# MEGA_shield_PORTS.net
KiCad netlist of a schematic drawn in EAGLE
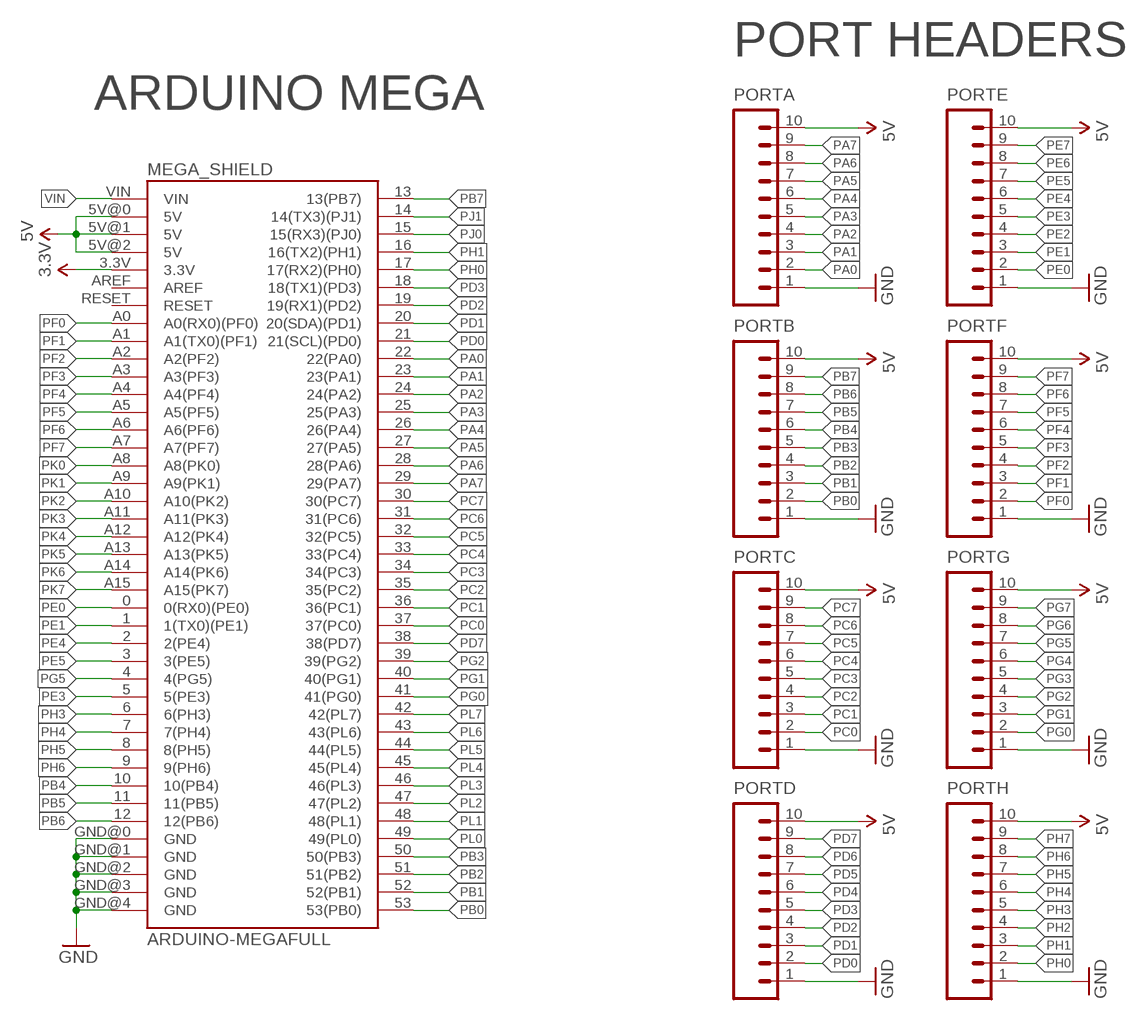
[diagram p0: schematic, sheet 1]

(export (version "E")
  (design (tool "Eeschema 10.0.6"))
  (components
    (comp (ref "MEGA_SHIELD")
      (value "ARDUINO-MEGAFULL")
      (footprint "eagle-import:ARDUINO_MEGA")
      (libsource (lib "eagle-import") (part "ARDUINO-MEGAFULL"))
    )
    (comp (ref "PORTA")
      (value "M10NO_SILK_PTH_FEMALE")
      (footprint "eagle-import:1X10_NO_SILK")
      (libsource (lib "eagle-import") (part "M10NO_SILK_PTH_FEMALE"))
    )
    (comp (ref "PORTB")
      (value "M10NO_SILK_PTH_FEMALE")
      (footprint "eagle-import:1X10_NO_SILK")
      (libsource (lib "eagle-import") (part "M10NO_SILK_PTH_FEMALE"))
    )
    (comp (ref "PORTC")
      (value "M10NO_SILK_PTH_FEMALE")
      (footprint "eagle-import:1X10_NO_SILK")
      (libsource (lib "eagle-import") (part "M10NO_SILK_PTH_FEMALE"))
    )
    (comp (ref "PORTD")
      (value "M10NO_SILK_PTH_FEMALE")
      (footprint "eagle-import:1X10_NO_SILK")
      (libsource (lib "eagle-import") (part "M10NO_SILK_PTH_FEMALE"))
    )
    (comp (ref "PORTE")
      (value "M10NO_SILK_PTH_FEMALE")
      (footprint "eagle-import:1X10_NO_SILK")
      (libsource (lib "eagle-import") (part "M10NO_SILK_PTH_FEMALE"))
    )
    (comp (ref "PORTF")
      (value "M10NO_SILK_PTH_FEMALE")
      (footprint "eagle-import:1X10_NO_SILK")
      (libsource (lib "eagle-import") (part "M10NO_SILK_PTH_FEMALE"))
    )
    (comp (ref "PORTG")
      (value "M10NO_SILK_PTH_FEMALE")
      (footprint "eagle-import:1X10_NO_SILK")
      (libsource (lib "eagle-import") (part "M10NO_SILK_PTH_FEMALE"))
    )
    (comp (ref "PORTH")
      (value "M10NO_SILK_PTH_FEMALE")
      (footprint "eagle-import:1X10_NO_SILK")
      (libsource (lib "eagle-import") (part "M10NO_SILK_PTH_FEMALE"))
    )
  )
  (nets
    (net (code "1") (name "3.3V") (class "Default")
      (node (ref "MEGA_SHIELD") (pin "3.3V") (pinfunction "3.3V_3.3V") (pintype "bidirectional"))
    )
    (net (code "2") (name "5V") (class "Default")
      (node (ref "MEGA_SHIELD") (pin "5V@0") (pinfunction "5V_5V@0") (pintype "bidirectional"))
      (node (ref "MEGA_SHIELD") (pin "5V@1") (pinfunction "5V_5V@1") (pintype "bidirectional"))
      (node (ref "MEGA_SHIELD") (pin "5V@2") (pinfunction "5V_5V@2") (pintype "bidirectional"))
      (node (ref "PORTA") (pin "10") (pinfunction "10_10") (pintype "passive"))
      (node (ref "PORTB") (pin "10") (pinfunction "10_10") (pintype "passive"))
      (node (ref "PORTC") (pin "10") (pinfunction "10_10") (pintype "passive"))
      (node (ref "PORTD") (pin "10") (pinfunction "10_10") (pintype "passive"))
      (node (ref "PORTE") (pin "10") (pinfunction "10_10") (pintype "passive"))
      (node (ref "PORTF") (pin "10") (pinfunction "10_10") (pintype "passive"))
      (node (ref "PORTG") (pin "10") (pinfunction "10_10") (pintype "passive"))
      (node (ref "PORTH") (pin "10") (pinfunction "10_10") (pintype "passive"))
    )
    (net (code "3") (name "GND") (class "Default")
      (node (ref "MEGA_SHIELD") (pin "GND@0") (pinfunction "GND_GND@0") (pintype "bidirectional"))
      (node (ref "MEGA_SHIELD") (pin "GND@1") (pinfunction "GND_GND@1") (pintype "bidirectional"))
      (node (ref "MEGA_SHIELD") (pin "GND@2") (pinfunction "GND_GND@2") (pintype "bidirectional"))
      (node (ref "MEGA_SHIELD") (pin "GND@3") (pinfunction "GND_GND@3") (pintype "bidirectional"))
      (node (ref "MEGA_SHIELD") (pin "GND@4") (pinfunction "GND_GND@4") (pintype "bidirectional"))
      (node (ref "PORTA") (pin "1") (pinfunction "1_1") (pintype "passive"))
      (node (ref "PORTB") (pin "1") (pinfunction "1_1") (pintype "passive"))
      (node (ref "PORTC") (pin "1") (pinfunction "1_1") (pintype "passive"))
      (node (ref "PORTD") (pin "1") (pinfunction "1_1") (pintype "passive"))
      (node (ref "PORTE") (pin "1") (pinfunction "1_1") (pintype "passive"))
      (node (ref "PORTF") (pin "1") (pinfunction "1_1") (pintype "passive"))
      (node (ref "PORTG") (pin "1") (pinfunction "1_1") (pintype "passive"))
      (node (ref "PORTH") (pin "1") (pinfunction "1_1") (pintype "passive"))
    )
    (net (code "4") (name "PA0") (class "Default")
      (node (ref "MEGA_SHIELD") (pin "22") (pinfunction "22(PA0)_22") (pintype "bidirectional"))
      (node (ref "PORTA") (pin "2") (pinfunction "2_2") (pintype "passive"))
    )
    (net (code "5") (name "PA1") (class "Default")
      (node (ref "MEGA_SHIELD") (pin "23") (pinfunction "23(PA1)_23") (pintype "bidirectional"))
      (node (ref "PORTA") (pin "3") (pinfunction "3_3") (pintype "passive"))
    )
    (net (code "6") (name "PA2") (class "Default")
      (node (ref "MEGA_SHIELD") (pin "24") (pinfunction "24(PA2)_24") (pintype "bidirectional"))
      (node (ref "PORTA") (pin "4") (pinfunction "4_4") (pintype "passive"))
    )
    (net (code "7") (name "PA3") (class "Default")
      (node (ref "MEGA_SHIELD") (pin "25") (pinfunction "25(PA3)_25") (pintype "bidirectional"))
      (node (ref "PORTA") (pin "5") (pinfunction "5_5") (pintype "passive"))
    )
    (net (code "8") (name "PA4") (class "Default")
      (node (ref "MEGA_SHIELD") (pin "26") (pinfunction "26(PA4)_26") (pintype "bidirectional"))
      (node (ref "PORTA") (pin "6") (pinfunction "6_6") (pintype "passive"))
    )
    (net (code "9") (name "PA5") (class "Default")
      (node (ref "MEGA_SHIELD") (pin "27") (pinfunction "27(PA5)_27") (pintype "bidirectional"))
      (node (ref "PORTA") (pin "7") (pinfunction "7_7") (pintype "passive"))
    )
    (net (code "10") (name "PA6") (class "Default")
      (node (ref "MEGA_SHIELD") (pin "28") (pinfunction "28(PA6)_28") (pintype "bidirectional"))
      (node (ref "PORTA") (pin "8") (pinfunction "8_8") (pintype "passive"))
    )
    (net (code "11") (name "PA7") (class "Default")
      (node (ref "MEGA_SHIELD") (pin "29") (pinfunction "29(PA7)_29") (pintype "bidirectional"))
      (node (ref "PORTA") (pin "9") (pinfunction "9_9") (pintype "passive"))
    )
    (net (code "12") (name "PB0") (class "Default")
      (node (ref "MEGA_SHIELD") (pin "53") (pinfunction "53(PB0)_53") (pintype "bidirectional"))
      (node (ref "PORTB") (pin "2") (pinfunction "2_2") (pintype "passive"))
    )
    (net (code "13") (name "PB1") (class "Default")
      (node (ref "MEGA_SHIELD") (pin "52") (pinfunction "52(PB1)_52") (pintype "bidirectional"))
      (node (ref "PORTB") (pin "3") (pinfunction "3_3") (pintype "passive"))
    )
    (net (code "14") (name "PB2") (class "Default")
      (node (ref "MEGA_SHIELD") (pin "51") (pinfunction "51(PB2)_51") (pintype "bidirectional"))
      (node (ref "PORTB") (pin "4") (pinfunction "4_4") (pintype "passive"))
    )
    (net (code "15") (name "PB3") (class "Default")
      (node (ref "MEGA_SHIELD") (pin "50") (pinfunction "50(PB3)_50") (pintype "bidirectional"))
      (node (ref "PORTB") (pin "5") (pinfunction "5_5") (pintype "passive"))
    )
    (net (code "16") (name "PB4") (class "Default")
      (node (ref "MEGA_SHIELD") (pin "10") (pinfunction "10(PB4)_10") (pintype "bidirectional"))
      (node (ref "PORTB") (pin "6") (pinfunction "6_6") (pintype "passive"))
    )
    (net (code "17") (name "PB5") (class "Default")
      (node (ref "MEGA_SHIELD") (pin "11") (pinfunction "11(PB5)_11") (pintype "bidirectional"))
      (node (ref "PORTB") (pin "7") (pinfunction "7_7") (pintype "passive"))
    )
    (net (code "18") (name "PB6") (class "Default")
      (node (ref "MEGA_SHIELD") (pin "12") (pinfunction "12(PB6)_12") (pintype "bidirectional"))
      (node (ref "PORTB") (pin "8") (pinfunction "8_8") (pintype "passive"))
    )
    (net (code "19") (name "PB7") (class "Default")
      (node (ref "MEGA_SHIELD") (pin "13") (pinfunction "13(PB7)_13") (pintype "bidirectional"))
      (node (ref "PORTB") (pin "9") (pinfunction "9_9") (pintype "passive"))
    )
    (net (code "20") (name "PC0") (class "Default")
      (node (ref "MEGA_SHIELD") (pin "37") (pinfunction "37(PC0)_37") (pintype "bidirectional"))
      (node (ref "PORTC") (pin "2") (pinfunction "2_2") (pintype "passive"))
    )
    (net (code "21") (name "PC1") (class "Default")
      (node (ref "MEGA_SHIELD") (pin "36") (pinfunction "36(PC1)_36") (pintype "bidirectional"))
      (node (ref "PORTC") (pin "3") (pinfunction "3_3") (pintype "passive"))
    )
    (net (code "22") (name "PC2") (class "Default")
      (node (ref "MEGA_SHIELD") (pin "35") (pinfunction "35(PC2)_35") (pintype "bidirectional"))
      (node (ref "PORTC") (pin "4") (pinfunction "4_4") (pintype "passive"))
    )
    (net (code "23") (name "PC3") (class "Default")
      (node (ref "MEGA_SHIELD") (pin "34") (pinfunction "34(PC3)_34") (pintype "bidirectional"))
      (node (ref "PORTC") (pin "5") (pinfunction "5_5") (pintype "passive"))
    )
    (net (code "24") (name "PC4") (class "Default")
      (node (ref "MEGA_SHIELD") (pin "33") (pinfunction "33(PC4)_33") (pintype "bidirectional"))
      (node (ref "PORTC") (pin "6") (pinfunction "6_6") (pintype "passive"))
    )
    (net (code "25") (name "PC5") (class "Default")
      (node (ref "MEGA_SHIELD") (pin "32") (pinfunction "32(PC5)_32") (pintype "bidirectional"))
      (node (ref "PORTC") (pin "7") (pinfunction "7_7") (pintype "passive"))
    )
    (net (code "26") (name "PC6") (class "Default")
      (node (ref "MEGA_SHIELD") (pin "31") (pinfunction "31(PC6)_31") (pintype "bidirectional"))
      (node (ref "PORTC") (pin "8") (pinfunction "8_8") (pintype "passive"))
    )
    (net (code "27") (name "PC7") (class "Default")
      (node (ref "MEGA_SHIELD") (pin "30") (pinfunction "30(PC7)_30") (pintype "bidirectional"))
      (node (ref "PORTC") (pin "9") (pinfunction "9_9") (pintype "passive"))
    )
    (net (code "28") (name "PD0") (class "Default")
      (node (ref "MEGA_SHIELD") (pin "21") (pinfunction "21(SCL)(PD0)_21") (pintype "bidirectional"))
      (node (ref "PORTD") (pin "2") (pinfunction "2_2") (pintype "passive"))
    )
    (net (code "29") (name "PD1") (class "Default")
      (node (ref "MEGA_SHIELD") (pin "20") (pinfunction "20(SDA)(PD1)_20") (pintype "bidirectional"))
      (node (ref "PORTD") (pin "3") (pinfunction "3_3") (pintype "passive"))
    )
    (net (code "30") (name "PD2") (class "Default")
      (node (ref "MEGA_SHIELD") (pin "19") (pinfunction "19(RX1)(PD2)_19") (pintype "bidirectional"))
      (node (ref "PORTD") (pin "4") (pinfunction "4_4") (pintype "passive"))
    )
    (net (code "31") (name "PD3") (class "Default")
      (node (ref "MEGA_SHIELD") (pin "18") (pinfunction "18(TX1)(PD3)_18") (pintype "bidirectional"))
      (node (ref "PORTD") (pin "5") (pinfunction "5_5") (pintype "passive"))
    )
    (net (code "32") (name "PD4") (class "Default")
      (node (ref "PORTD") (pin "6") (pinfunction "6_6") (pintype "passive"))
    )
    (net (code "33") (name "PD5") (class "Default")
      (node (ref "PORTD") (pin "7") (pinfunction "7_7") (pintype "passive"))
    )
    (net (code "34") (name "PD6") (class "Default")
      (node (ref "PORTD") (pin "8") (pinfunction "8_8") (pintype "passive"))
    )
    (net (code "35") (name "PD7") (class "Default")
      (node (ref "MEGA_SHIELD") (pin "38") (pinfunction "38(PD7)_38") (pintype "bidirectional"))
      (node (ref "PORTD") (pin "9") (pinfunction "9_9") (pintype "passive"))
    )
    (net (code "36") (name "PE0") (class "Default")
      (node (ref "MEGA_SHIELD") (pin "0") (pinfunction "0(RX0)(PE0)_0") (pintype "bidirectional"))
      (node (ref "PORTE") (pin "2") (pinfunction "2_2") (pintype "passive"))
    )
    (net (code "37") (name "PE1") (class "Default")
      (node (ref "MEGA_SHIELD") (pin "1") (pinfunction "1(TX0)(PE1)_1") (pintype "bidirectional"))
      (node (ref "PORTE") (pin "3") (pinfunction "3_3") (pintype "passive"))
    )
    (net (code "38") (name "PE2") (class "Default")
      (node (ref "PORTE") (pin "4") (pinfunction "4_4") (pintype "passive"))
    )
    (net (code "39") (name "PE3") (class "Default")
      (node (ref "MEGA_SHIELD") (pin "5") (pinfunction "5(PE3)_5") (pintype "bidirectional"))
      (node (ref "PORTE") (pin "5") (pinfunction "5_5") (pintype "passive"))
    )
    (net (code "40") (name "PE4") (class "Default")
      (node (ref "MEGA_SHIELD") (pin "2") (pinfunction "2(PE4)_2") (pintype "bidirectional"))
      (node (ref "PORTE") (pin "6") (pinfunction "6_6") (pintype "passive"))
    )
    (net (code "41") (name "PE5") (class "Default")
      (node (ref "MEGA_SHIELD") (pin "3") (pinfunction "3(PE5)_3") (pintype "bidirectional"))
      (node (ref "PORTE") (pin "7") (pinfunction "7_7") (pintype "passive"))
    )
    (net (code "42") (name "PE6") (class "Default")
      (node (ref "PORTE") (pin "8") (pinfunction "8_8") (pintype "passive"))
    )
    (net (code "43") (name "PE7") (class "Default")
      (node (ref "PORTE") (pin "9") (pinfunction "9_9") (pintype "passive"))
    )
    (net (code "44") (name "PF0") (class "Default")
      (node (ref "MEGA_SHIELD") (pin "A0") (pinfunction "A0(RX0)(PF0)_A0") (pintype "bidirectional"))
      (node (ref "PORTF") (pin "2") (pinfunction "2_2") (pintype "passive"))
    )
    (net (code "45") (name "PF1") (class "Default")
      (node (ref "MEGA_SHIELD") (pin "A1") (pinfunction "A1(TX0)(PF1)_A1") (pintype "bidirectional"))
      (node (ref "PORTF") (pin "3") (pinfunction "3_3") (pintype "passive"))
    )
    (net (code "46") (name "PF2") (class "Default")
      (node (ref "MEGA_SHIELD") (pin "A2") (pinfunction "A2(PF2)_A2") (pintype "bidirectional"))
      (node (ref "PORTF") (pin "4") (pinfunction "4_4") (pintype "passive"))
    )
    (net (code "47") (name "PF3") (class "Default")
      (node (ref "MEGA_SHIELD") (pin "A3") (pinfunction "A3(PF3)_A3") (pintype "bidirectional"))
      (node (ref "PORTF") (pin "5") (pinfunction "5_5") (pintype "passive"))
    )
    (net (code "48") (name "PF4") (class "Default")
      (node (ref "MEGA_SHIELD") (pin "A4") (pinfunction "A4(PF4)_A4") (pintype "bidirectional"))
      (node (ref "PORTF") (pin "6") (pinfunction "6_6") (pintype "passive"))
    )
    (net (code "49") (name "PF5") (class "Default")
      (node (ref "MEGA_SHIELD") (pin "A5") (pinfunction "A5(PF5)_A5") (pintype "bidirectional"))
      (node (ref "PORTF") (pin "7") (pinfunction "7_7") (pintype "passive"))
    )
    (net (code "50") (name "PF6") (class "Default")
      (node (ref "MEGA_SHIELD") (pin "A6") (pinfunction "A6(PF6)_A6") (pintype "bidirectional"))
      (node (ref "PORTF") (pin "8") (pinfunction "8_8") (pintype "passive"))
    )
    (net (code "51") (name "PF7") (class "Default")
      (node (ref "MEGA_SHIELD") (pin "A7") (pinfunction "A7(PF7)_A7") (pintype "bidirectional"))
      (node (ref "PORTF") (pin "9") (pinfunction "9_9") (pintype "passive"))
    )
    (net (code "52") (name "PG0") (class "Default")
      (node (ref "MEGA_SHIELD") (pin "41") (pinfunction "41(PG0)_41") (pintype "bidirectional"))
      (node (ref "PORTG") (pin "2") (pinfunction "2_2") (pintype "passive"))
    )
    (net (code "53") (name "PG1") (class "Default")
      (node (ref "MEGA_SHIELD") (pin "40") (pinfunction "40(PG1)_40") (pintype "bidirectional"))
      (node (ref "PORTG") (pin "3") (pinfunction "3_3") (pintype "passive"))
    )
    (net (code "54") (name "PG2") (class "Default")
      (node (ref "MEGA_SHIELD") (pin "39") (pinfunction "39(PG2)_39") (pintype "bidirectional"))
      (node (ref "PORTG") (pin "4") (pinfunction "4_4") (pintype "passive"))
    )
    (net (code "55") (name "PG3") (class "Default")
      (node (ref "PORTG") (pin "5") (pinfunction "5_5") (pintype "passive"))
    )
    (net (code "56") (name "PG4") (class "Default")
      (node (ref "PORTG") (pin "6") (pinfunction "6_6") (pintype "passive"))
    )
    (net (code "57") (name "PG5") (class "Default")
      (node (ref "MEGA_SHIELD") (pin "4") (pinfunction "4(PG5)_4") (pintype "bidirectional"))
      (node (ref "PORTG") (pin "7") (pinfunction "7_7") (pintype "passive"))
    )
    (net (code "58") (name "PG6") (class "Default")
      (node (ref "PORTG") (pin "8") (pinfunction "8_8") (pintype "passive"))
    )
    (net (code "59") (name "PG7") (class "Default")
      (node (ref "PORTG") (pin "9") (pinfunction "9_9") (pintype "passive"))
    )
    (net (code "60") (name "PH0") (class "Default")
      (node (ref "MEGA_SHIELD") (pin "17") (pinfunction "17(RX2)(PH0)_17") (pintype "bidirectional"))
      (node (ref "PORTH") (pin "2") (pinfunction "2_2") (pintype "passive"))
    )
    (net (code "61") (name "PH1") (class "Default")
      (node (ref "MEGA_SHIELD") (pin "16") (pinfunction "16(TX2)(PH1)_16") (pintype "bidirectional"))
      (node (ref "PORTH") (pin "3") (pinfunction "3_3") (pintype "passive"))
    )
    (net (code "62") (name "PH2") (class "Default")
      (node (ref "PORTH") (pin "4") (pinfunction "4_4") (pintype "passive"))
    )
    (net (code "63") (name "PH3") (class "Default")
      (node (ref "MEGA_SHIELD") (pin "6") (pinfunction "6(PH3)_6") (pintype "bidirectional"))
      (node (ref "PORTH") (pin "5") (pinfunction "5_5") (pintype "passive"))
    )
    (net (code "64") (name "PH4") (class "Default")
      (node (ref "MEGA_SHIELD") (pin "7") (pinfunction "7(PH4)_7") (pintype "bidirectional"))
      (node (ref "PORTH") (pin "6") (pinfunction "6_6") (pintype "passive"))
    )
    (net (code "65") (name "PH5") (class "Default")
      (node (ref "MEGA_SHIELD") (pin "8") (pinfunction "8(PH5)_8") (pintype "bidirectional"))
      (node (ref "PORTH") (pin "7") (pinfunction "7_7") (pintype "passive"))
    )
    (net (code "66") (name "PH6") (class "Default")
      (node (ref "MEGA_SHIELD") (pin "9") (pinfunction "9(PH6)_9") (pintype "bidirectional"))
      (node (ref "PORTH") (pin "8") (pinfunction "8_8") (pintype "passive"))
    )
    (net (code "67") (name "PH7") (class "Default")
      (node (ref "PORTH") (pin "9") (pinfunction "9_9") (pintype "passive"))
    )
    (net (code "68") (name "PJ0") (class "Default")
      (node (ref "MEGA_SHIELD") (pin "15") (pinfunction "15(RX3)(PJ0)_15") (pintype "bidirectional"))
    )
    (net (code "69") (name "PJ1") (class "Default")
      (node (ref "MEGA_SHIELD") (pin "14") (pinfunction "14(TX3)(PJ1)_14") (pintype "bidirectional"))
    )
    (net (code "70") (name "PK0") (class "Default")
      (node (ref "MEGA_SHIELD") (pin "A8") (pinfunction "A8(PK0)_A8") (pintype "bidirectional"))
    )
    (net (code "71") (name "PK1") (class "Default")
      (node (ref "MEGA_SHIELD") (pin "A9") (pinfunction "A9(PK1)_A9") (pintype "bidirectional"))
    )
    (net (code "72") (name "PK2") (class "Default")
      (node (ref "MEGA_SHIELD") (pin "A10") (pinfunction "A10(PK2)_A10") (pintype "bidirectional"))
    )
    (net (code "73") (name "PK3") (class "Default")
      (node (ref "MEGA_SHIELD") (pin "A11") (pinfunction "A11(PK3)_A11") (pintype "bidirectional"))
    )
    (net (code "74") (name "PK4") (class "Default")
      (node (ref "MEGA_SHIELD") (pin "A12") (pinfunction "A12(PK4)_A12") (pintype "bidirectional"))
    )
    (net (code "75") (name "PK5") (class "Default")
      (node (ref "MEGA_SHIELD") (pin "A13") (pinfunction "A13(PK5)_A13") (pintype "bidirectional"))
    )
    (net (code "76") (name "PK6") (class "Default")
      (node (ref "MEGA_SHIELD") (pin "A14") (pinfunction "A14(PK6)_A14") (pintype "bidirectional"))
    )
    (net (code "77") (name "PK7") (class "Default")
      (node (ref "MEGA_SHIELD") (pin "A15") (pinfunction "A15(PK7)_A15") (pintype "bidirectional"))
    )
    (net (code "78") (name "PL0") (class "Default")
      (node (ref "MEGA_SHIELD") (pin "49") (pinfunction "49(PL0)_49") (pintype "bidirectional"))
    )
    (net (code "79") (name "PL1") (class "Default")
      (node (ref "MEGA_SHIELD") (pin "48") (pinfunction "48(PL1)_48") (pintype "bidirectional"))
    )
    (net (code "80") (name "PL2") (class "Default")
      (node (ref "MEGA_SHIELD") (pin "47") (pinfunction "47(PL2)_47") (pintype "bidirectional"))
    )
    (net (code "81") (name "PL3") (class "Default")
      (node (ref "MEGA_SHIELD") (pin "46") (pinfunction "46(PL3)_46") (pintype "bidirectional"))
    )
    (net (code "82") (name "PL4") (class "Default")
      (node (ref "MEGA_SHIELD") (pin "45") (pinfunction "45(PL4)_45") (pintype "bidirectional"))
    )
    (net (code "83") (name "PL5") (class "Default")
      (node (ref "MEGA_SHIELD") (pin "44") (pinfunction "44(PL5)_44") (pintype "bidirectional"))
    )
    (net (code "84") (name "PL6") (class "Default")
      (node (ref "MEGA_SHIELD") (pin "43") (pinfunction "43(PL6)_43") (pintype "bidirectional"))
    )
    (net (code "85") (name "PL7") (class "Default")
      (node (ref "MEGA_SHIELD") (pin "42") (pinfunction "42(PL7)_42") (pintype "bidirectional"))
    )
    (net (code "86") (name "VIN") (class "Default")
      (node (ref "MEGA_SHIELD") (pin "VIN") (pinfunction "VIN_VIN") (pintype "bidirectional"))
    )
    (net (code "87") (name "unconnected-(MEGA_SHIELD-PadAREF)") (class "Default")
      (node (ref "MEGA_SHIELD") (pin "AREF") (pinfunction "AREF_AREF") (pintype "bidirectional"))
    )
    (net (code "88") (name "unconnected-(MEGA_SHIELD-PadRESET)") (class "Default")
      (node (ref "MEGA_SHIELD") (pin "RESET") (pinfunction "RESET_RESET") (pintype "bidirectional"))
    )
  )
)
